# HiveX-Schematic-09.net
KiCad netlist of a schematic drawn in EAGLE
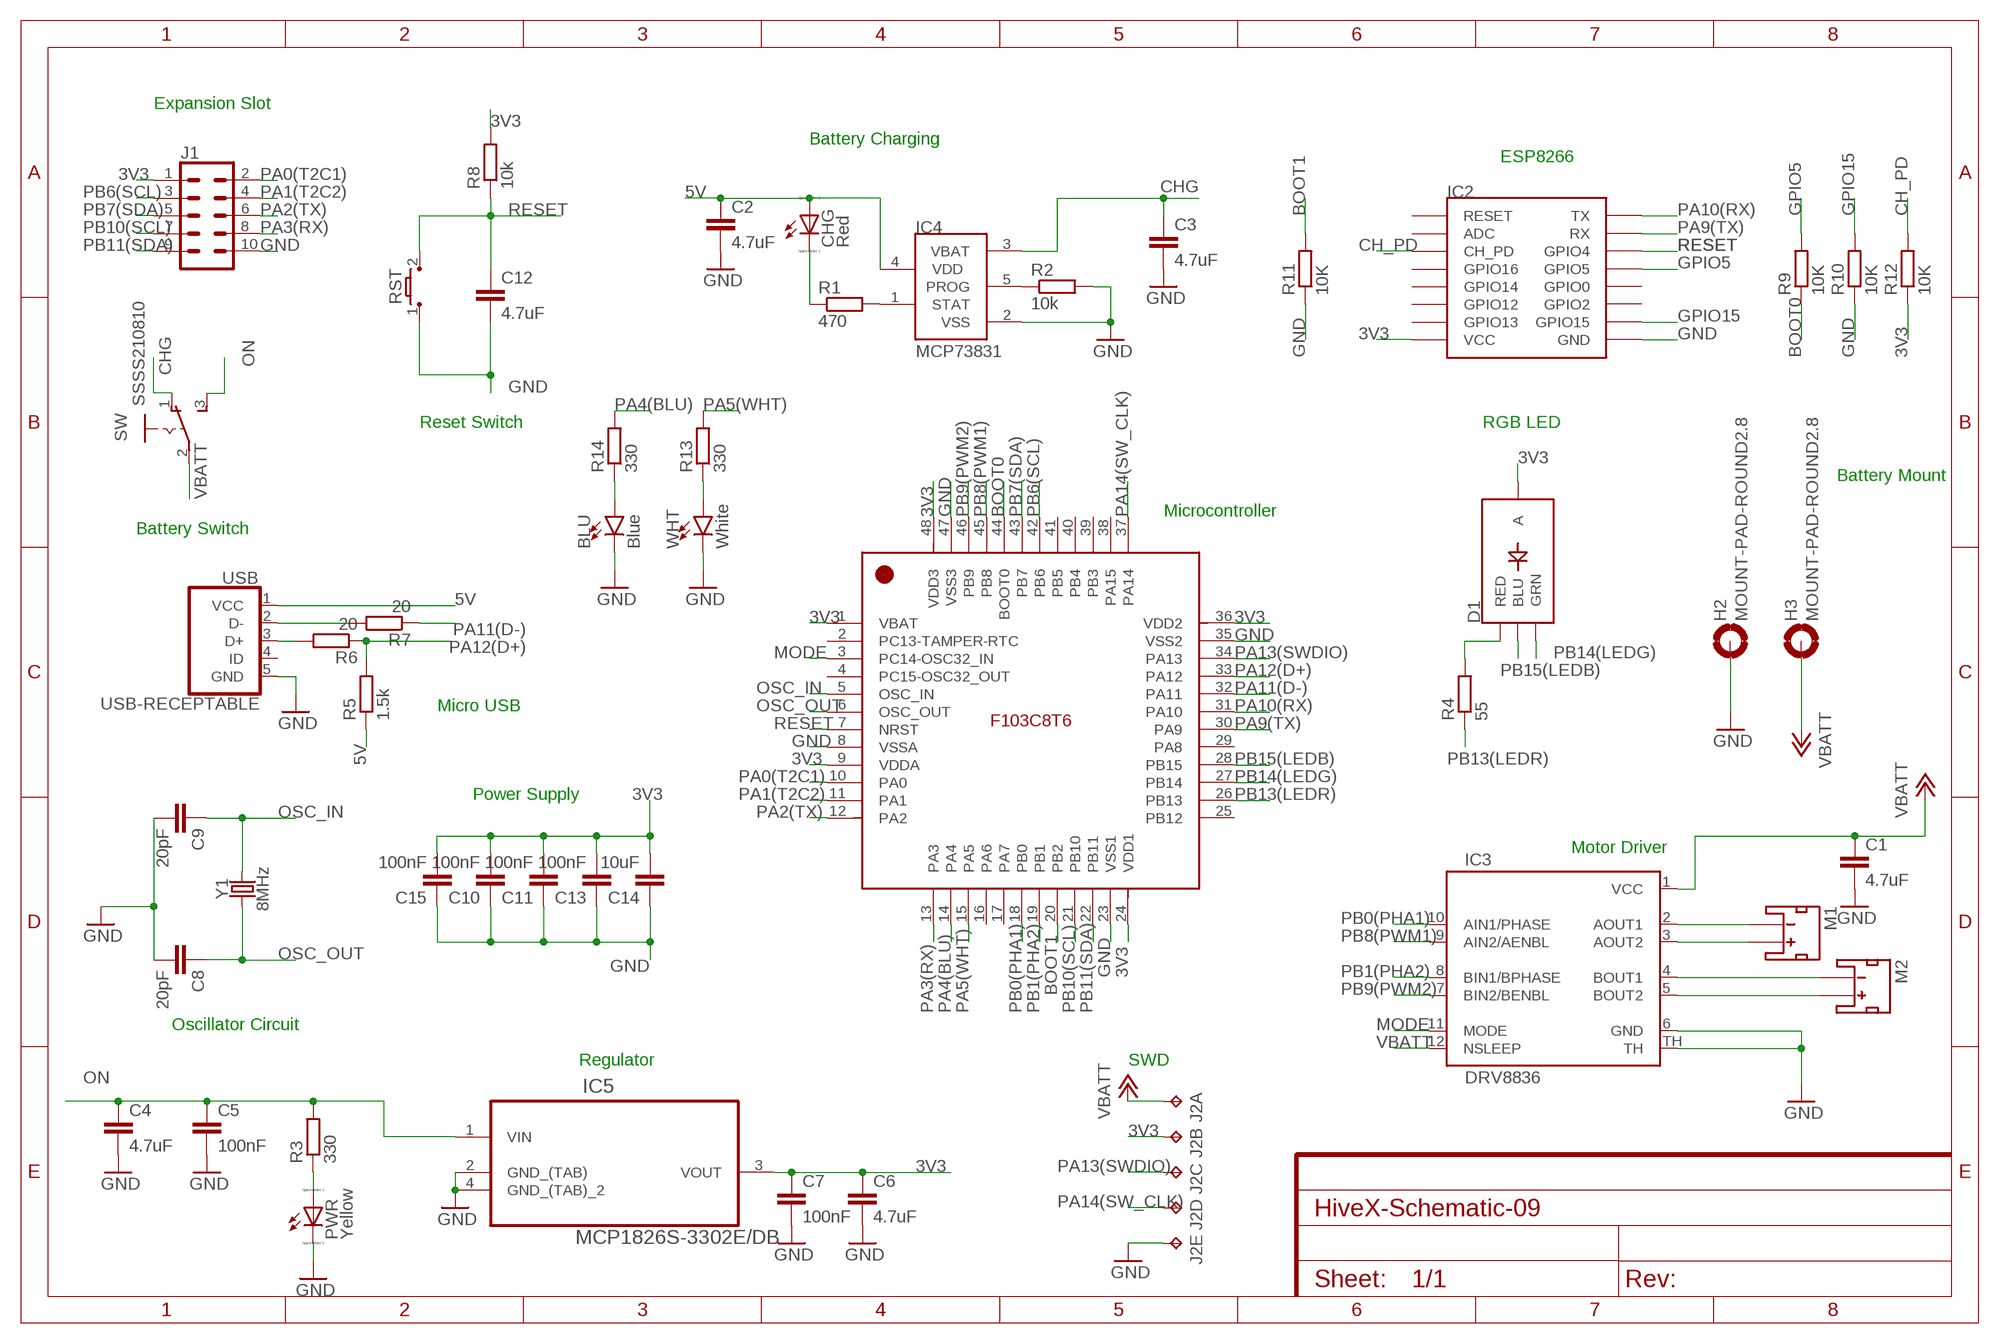
[diagram p0: schematic, sheet 1]

(export (version "E")
  (design (tool "Eeschema 10.0.6"))
  (components
    (comp (ref "BLU")
      (value "Blue")
      (footprint "eagle-import:LED-0603")
      (libsource (lib "eagle-import") (part "LED-BLUE0603"))
    )
    (comp (ref "C1")
      (value "4.7uF")
      (footprint "eagle-import:0603-CAP")
      (libsource (lib "eagle-import") (part "CAP0603-CAP"))
    )
    (comp (ref "C2")
      (value "4.7uF")
      (footprint "eagle-import:0603-CAP")
      (libsource (lib "eagle-import") (part "CAP0603-CAP"))
    )
    (comp (ref "C3")
      (value "4.7uF")
      (footprint "eagle-import:0603-CAP")
      (libsource (lib "eagle-import") (part "CAP0603-CAP"))
    )
    (comp (ref "C4")
      (value "4.7uF")
      (footprint "eagle-import:0603-CAP")
      (libsource (lib "eagle-import") (part "CAP0603-CAP"))
    )
    (comp (ref "C5")
      (value "100nF")
      (footprint "eagle-import:0603-CAP")
      (libsource (lib "eagle-import") (part "CAP0603-CAP"))
    )
    (comp (ref "C6")
      (value "4.7uF")
      (footprint "eagle-import:0603-CAP")
      (libsource (lib "eagle-import") (part "CAP0603-CAP"))
    )
    (comp (ref "C7")
      (value "100nF")
      (footprint "eagle-import:0603-CAP")
      (libsource (lib "eagle-import") (part "CAP0603-CAP"))
    )
    (comp (ref "C8")
      (value "20pF")
      (footprint "eagle-import:0603-CAP")
      (libsource (lib "eagle-import") (part "CAP0603-CAP"))
    )
    (comp (ref "C9")
      (value "20pF")
      (footprint "eagle-import:0603-CAP")
      (libsource (lib "eagle-import") (part "CAP0603-CAP"))
    )
    (comp (ref "C10")
      (value "100nF")
      (footprint "eagle-import:0603-CAP")
      (libsource (lib "eagle-import") (part "CAP0603-CAP"))
    )
    (comp (ref "C11")
      (value "100nF")
      (footprint "eagle-import:0603-CAP")
      (libsource (lib "eagle-import") (part "CAP0603-CAP"))
    )
    (comp (ref "C12")
      (value "4.7uF")
      (footprint "eagle-import:0603-CAP")
      (libsource (lib "eagle-import") (part "CAP0603-CAP"))
    )
    (comp (ref "C13")
      (value "100nF")
      (footprint "eagle-import:0603-CAP")
      (libsource (lib "eagle-import") (part "CAP0603-CAP"))
    )
    (comp (ref "C14")
      (value "10uF")
      (footprint "eagle-import:0603-CAP")
      (libsource (lib "eagle-import") (part "CAP0603-CAP"))
    )
    (comp (ref "C15")
      (value "100nF")
      (footprint "eagle-import:0603-CAP")
      (libsource (lib "eagle-import") (part "CAP0603-CAP"))
    )
    (comp (ref "CHG")
      (value "Red")
      (footprint "eagle-import:LED_SML0603")
      (libsource (lib "eagle-import") (part "LED_ESML0603"))
    )
    (comp (ref "D1")
      (value "LED-RGB-CASMD")
      (footprint "eagle-import:LED-TRICOLOR-SMD")
      (libsource (lib "eagle-import") (part "LED-RGB-CASMD"))
    )
    (comp (ref "H2")
      (value "MOUNT-PAD-ROUND2.8")
      (footprint "eagle-import:2,8-PAD")
      (libsource (lib "eagle-import") (part "MOUNT-PAD-ROUND2.8"))
    )
    (comp (ref "H3")
      (value "MOUNT-PAD-ROUND2.8")
      (footprint "eagle-import:2,8-PAD")
      (libsource (lib "eagle-import") (part "MOUNT-PAD-ROUND2.8"))
    )
    (comp (ref "IC1")
      (value "STM32F103C8T6")
      (footprint "eagle-import:LQFP48_7X7MM_0.5MMPP")
      (fields (field (name "MF") "STMicroelectronics"))
      (libsource (lib "eagle-import") (part "STM32F103C8T6"))
    )
    (comp (ref "IC2")
      (value "ESP12")
      (footprint "eagle-import:ESP12")
      (libsource (lib "eagle-import") (part "ESP12"))
    )
    (comp (ref "IC3")
      (value "DRV8836")
      (footprint "eagle-import:12WSON")
      (libsource (lib "eagle-import") (part "DRV8836"))
    )
    (comp (ref "IC4")
      (value "MCP73831")
      (footprint "eagle-import:SOT23-5L")
      (libsource (lib "eagle-import") (part "MCP73831"))
    )
    (comp (ref "IC5")
      (value "MCP1826S-3302E/DB")
      (footprint "eagle-import:SOT230P700X180-4N")
      (fields (field (name "MF") "Microchip"))
      (libsource (lib "eagle-import") (part "MCP1826S-3302E/DB"))
    )
    (comp (ref "J1")
      (value "CONN_05X2PTH")
      (footprint "eagle-import:2X5")
      (libsource (lib "eagle-import") (part "CONN_05X2PTH"))
    )
    (comp (ref "J2")
      (value "TP5P5-25-13")
      (footprint "eagle-import:P5-25-13")
      (libsource (lib "eagle-import") (part "TP5P5-25-13"))
    )
    (comp (ref "M1")
      (value "JST_2MM_MALE")
      (footprint "eagle-import:JST-2-SMD")
      (libsource (lib "eagle-import") (part "JST_2MM_MALE"))
    )
    (comp (ref "M2")
      (value "JST_2MM_MALE")
      (footprint "eagle-import:JST-2-SMD")
      (libsource (lib "eagle-import") (part "JST_2MM_MALE"))
    )
    (comp (ref "PWR")
      (value "Yellow")
      (footprint "eagle-import:LED_SML0603")
      (libsource (lib "eagle-import") (part "LED_ESML0603"))
    )
    (comp (ref "R1")
      (value "470")
      (footprint "eagle-import:R0603")
      (libsource (lib "eagle-import") (part "resistor_348_R-EU_R0603"))
    )
    (comp (ref "R2")
      (value "10k")
      (footprint "eagle-import:R0603")
      (libsource (lib "eagle-import") (part "resistor_348_R-EU_R0603"))
    )
    (comp (ref "R3")
      (value "330")
      (footprint "eagle-import:R0603")
      (libsource (lib "eagle-import") (part "resistor_348_R-EU_R0603"))
    )
    (comp (ref "R4")
      (value "55")
      (footprint "eagle-import:R0603")
      (libsource (lib "eagle-import") (part "resistor_348_R-EU_R0603"))
    )
    (comp (ref "R5")
      (value "1.5k")
      (footprint "eagle-import:R0603")
      (libsource (lib "eagle-import") (part "resistor_348_R-EU_R0603"))
    )
    (comp (ref "R6")
      (value "20")
      (footprint "eagle-import:R0603")
      (libsource (lib "eagle-import") (part "resistor_348_R-EU_R0603"))
    )
    (comp (ref "R7")
      (value "20")
      (footprint "eagle-import:R0603")
      (libsource (lib "eagle-import") (part "resistor_348_R-EU_R0603"))
    )
    (comp (ref "R8")
      (value "10k")
      (footprint "eagle-import:R0603")
      (libsource (lib "eagle-import") (part "resistor_348_R-EU_R0603"))
    )
    (comp (ref "R9")
      (value "10K")
      (footprint "eagle-import:R0603")
      (libsource (lib "eagle-import") (part "R-EU_R0603"))
    )
    (comp (ref "R10")
      (value "10K")
      (footprint "eagle-import:R0603")
      (libsource (lib "eagle-import") (part "R-EU_R0603"))
    )
    (comp (ref "R11")
      (value "10K")
      (footprint "eagle-import:R0603")
      (libsource (lib "eagle-import") (part "R-EU_R0603"))
    )
    (comp (ref "R12")
      (value "10K")
      (footprint "eagle-import:R0603")
      (libsource (lib "eagle-import") (part "R-EU_R0603"))
    )
    (comp (ref "R13")
      (value "330")
      (footprint "eagle-import:R0603")
      (libsource (lib "eagle-import") (part "resistor_348_R-EU_R0603"))
    )
    (comp (ref "R14")
      (value "330")
      (footprint "eagle-import:R0603")
      (libsource (lib "eagle-import") (part "resistor_348_R-EU_R0603"))
    )
    (comp (ref "RST")
      (value "TL3302-J")
      (footprint "eagle-import:TL3303_J")
      (libsource (lib "eagle-import") (part "TL3302-J"))
    )
    (comp (ref "SW")
      (value "SSSS210810")
      (footprint "eagle-import:SSSS210810")
      (libsource (lib "eagle-import") (part "SSSS210810"))
    )
    (comp (ref "USB")
      (value "USB-RECEPTABLE")
      (footprint "eagle-import:FCI-10103594-0001LF")
      (libsource (lib "eagle-import") (part "USB-RECEPTABLE"))
    )
    (comp (ref "WHT")
      (value "White")
      (footprint "eagle-import:LED-0603")
      (libsource (lib "eagle-import") (part "LED-WHITE0603"))
    )
    (comp (ref "Y1")
      (value "8MHz")
      (footprint "eagle-import:CRYSTAL-SMD-5X3.2-4PAD")
      (libsource (lib "eagle-import") (part "CRYSTAL-8MHZSMD-5X3.2"))
    )
  )
  (nets
    (net (code "1") (name "/3V3") (class "Default")
      (node (ref "C10") (pin "2") (pinfunction "2_2") (pintype "passive"))
      (node (ref "C11") (pin "2") (pinfunction "2_2") (pintype "passive"))
      (node (ref "C13") (pin "2") (pinfunction "2_2") (pintype "passive"))
      (node (ref "C14") (pin "2") (pinfunction "2_2") (pintype "passive"))
      (node (ref "C15") (pin "2") (pinfunction "2_2") (pintype "passive"))
      (node (ref "C6") (pin "1") (pinfunction "1_1") (pintype "passive"))
      (node (ref "C7") (pin "1") (pinfunction "1_1") (pintype "passive"))
      (node (ref "D1") (pin "A") (pinfunction "A_A") (pintype "bidirectional"))
      (node (ref "IC1") (pin "1") (pinfunction "VBAT_1") (pintype "bidirectional"))
      (node (ref "IC1") (pin "24") (pinfunction "VDD1_24") (pintype "bidirectional"))
      (node (ref "IC1") (pin "36") (pinfunction "VDD2_36") (pintype "bidirectional"))
      (node (ref "IC1") (pin "48") (pinfunction "VDD3_48") (pintype "bidirectional"))
      (node (ref "IC1") (pin "9") (pinfunction "VDDA_9") (pintype "bidirectional"))
      (node (ref "IC2") (pin "VCC") (pinfunction "VCC_VCC") (pintype "bidirectional"))
      (node (ref "IC5") (pin "3") (pinfunction "VOUT_3") (pintype "output"))
      (node (ref "J1") (pin "1") (pinfunction "1_1") (pintype "passive"))
      (node (ref "J2") (pin "TP-2") (pinfunction "TP_TP-2") (pintype "input"))
      (node (ref "R12") (pin "1") (pinfunction "1_1") (pintype "passive"))
      (node (ref "R8") (pin "2") (pinfunction "2_2") (pintype "passive"))
    )
    (net (code "2") (name "/5V") (class "Default")
      (node (ref "C2") (pin "1") (pinfunction "1_1") (pintype "passive"))
      (node (ref "CHG") (pin "A") (pinfunction "A_A") (pintype "passive"))
      (node (ref "IC4") (pin "4") (pinfunction "VDD_4") (pintype "bidirectional"))
      (node (ref "R5") (pin "1") (pinfunction "1_1") (pintype "passive"))
      (node (ref "USB") (pin "1") (pinfunction "VCC_1") (pintype "bidirectional"))
    )
    (net (code "3") (name "/BOOT0") (class "Default")
      (node (ref "IC1") (pin "44") (pinfunction "BOOT0_44") (pintype "bidirectional"))
      (node (ref "R9") (pin "1") (pinfunction "1_1") (pintype "passive"))
    )
    (net (code "4") (name "/BOOT1") (class "Default")
      (node (ref "IC1") (pin "20") (pinfunction "PB2_20") (pintype "bidirectional"))
      (node (ref "R11") (pin "2") (pinfunction "2_2") (pintype "passive"))
    )
    (net (code "5") (name "/CHG") (class "Default")
      (node (ref "C3") (pin "1") (pinfunction "1_1") (pintype "passive"))
      (node (ref "IC4") (pin "3") (pinfunction "VBAT_3") (pintype "bidirectional"))
      (node (ref "SW") (pin "1") (pinfunction "NC_1") (pintype "passive"))
    )
    (net (code "6") (name "/CH_PD") (class "Default")
      (node (ref "IC2") (pin "CH_PD") (pinfunction "CH_PD_CH_PD") (pintype "bidirectional"))
      (node (ref "R12") (pin "2") (pinfunction "2_2") (pintype "passive"))
    )
    (net (code "7") (name "/GPIO5") (class "Default")
      (node (ref "IC2") (pin "GPIO5") (pinfunction "GPIO5_GPIO5") (pintype "bidirectional"))
      (node (ref "R9") (pin "2") (pinfunction "2_2") (pintype "passive"))
    )
    (net (code "8") (name "/GPIO15") (class "Default")
      (node (ref "IC2") (pin "GPIO15") (pinfunction "GPIO15_GPIO15") (pintype "bidirectional"))
      (node (ref "R10") (pin "2") (pinfunction "2_2") (pintype "passive"))
    )
    (net (code "9") (name "/MODE") (class "Default")
      (node (ref "IC1") (pin "3") (pinfunction "PC14-OSC32_IN_3") (pintype "bidirectional"))
      (node (ref "IC3") (pin "11") (pinfunction "MODE_11") (pintype "bidirectional"))
    )
    (net (code "10") (name "/ON") (class "Default")
      (node (ref "C4") (pin "1") (pinfunction "1_1") (pintype "passive"))
      (node (ref "C5") (pin "1") (pinfunction "1_1") (pintype "passive"))
      (node (ref "IC5") (pin "1") (pinfunction "VIN_1") (pintype "input"))
      (node (ref "R3") (pin "2") (pinfunction "2_2") (pintype "passive"))
      (node (ref "SW") (pin "3") (pinfunction "NO_3") (pintype "passive"))
    )
    (net (code "11") (name "/OSC_IN") (class "Default")
      (node (ref "C9") (pin "1") (pinfunction "1_1") (pintype "passive"))
      (node (ref "IC1") (pin "5") (pinfunction "OSC_IN_5") (pintype "bidirectional"))
      (node (ref "Y1") (pin "3") (pinfunction "2_3") (pintype "passive"))
    )
    (net (code "12") (name "/OSC_OUT") (class "Default")
      (node (ref "C8") (pin "1") (pinfunction "1_1") (pintype "passive"))
      (node (ref "IC1") (pin "6") (pinfunction "OSC_OUT_6") (pintype "bidirectional"))
      (node (ref "Y1") (pin "1") (pinfunction "1_1") (pintype "passive"))
    )
    (net (code "13") (name "/PA0(T2C1)") (class "Default")
      (node (ref "IC1") (pin "10") (pinfunction "PA0_10") (pintype "bidirectional"))
      (node (ref "J1") (pin "2") (pinfunction "2_2") (pintype "passive"))
    )
    (net (code "14") (name "/PA1(T2C2)") (class "Default")
      (node (ref "IC1") (pin "11") (pinfunction "PA1_11") (pintype "bidirectional"))
      (node (ref "J1") (pin "4") (pinfunction "4_4") (pintype "passive"))
    )
    (net (code "15") (name "/PA2(TX)") (class "Default")
      (node (ref "IC1") (pin "12") (pinfunction "PA2_12") (pintype "bidirectional"))
      (node (ref "J1") (pin "6") (pinfunction "6_6") (pintype "passive"))
    )
    (net (code "16") (name "/PA3(RX)") (class "Default")
      (node (ref "IC1") (pin "13") (pinfunction "PA3_13") (pintype "bidirectional"))
      (node (ref "J1") (pin "8") (pinfunction "8_8") (pintype "passive"))
    )
    (net (code "17") (name "/PA4(BLU)") (class "Default")
      (node (ref "IC1") (pin "14") (pinfunction "PA4_14") (pintype "bidirectional"))
      (node (ref "R14") (pin "2") (pinfunction "2_2") (pintype "passive"))
    )
    (net (code "18") (name "/PA5(WHT)") (class "Default")
      (node (ref "IC1") (pin "15") (pinfunction "PA5_15") (pintype "bidirectional"))
      (node (ref "R13") (pin "2") (pinfunction "2_2") (pintype "passive"))
    )
    (net (code "19") (name "/PA9(TX)") (class "Default")
      (node (ref "IC1") (pin "30") (pinfunction "PA9_30") (pintype "bidirectional"))
      (node (ref "IC2") (pin "RX") (pinfunction "RX_RX") (pintype "bidirectional"))
    )
    (net (code "20") (name "/PA10(RX)") (class "Default")
      (node (ref "IC1") (pin "31") (pinfunction "PA10_31") (pintype "bidirectional"))
      (node (ref "IC2") (pin "TX") (pinfunction "TX_TX") (pintype "bidirectional"))
    )
    (net (code "21") (name "/PA11(D-)") (class "Default")
      (node (ref "IC1") (pin "32") (pinfunction "PA11_32") (pintype "bidirectional"))
      (node (ref "R7") (pin "1") (pinfunction "1_1") (pintype "passive"))
    )
    (net (code "22") (name "/PA12(D+)") (class "Default")
      (node (ref "IC1") (pin "33") (pinfunction "PA12_33") (pintype "bidirectional"))
      (node (ref "R5") (pin "2") (pinfunction "2_2") (pintype "passive"))
      (node (ref "R6") (pin "1") (pinfunction "1_1") (pintype "passive"))
    )
    (net (code "23") (name "/PA13(SWDIO)") (class "Default")
      (node (ref "IC1") (pin "34") (pinfunction "PA13_34") (pintype "bidirectional"))
      (node (ref "J2") (pin "TP-3") (pinfunction "TP_TP-3") (pintype "input"))
    )
    (net (code "24") (name "/PA14(SW_CLK)") (class "Default")
      (node (ref "IC1") (pin "37") (pinfunction "PA14_37") (pintype "bidirectional"))
      (node (ref "J2") (pin "TP-4") (pinfunction "TP_TP-4") (pintype "input"))
    )
    (net (code "25") (name "/PB0(PHA1)") (class "Default")
      (node (ref "IC1") (pin "18") (pinfunction "PB0_18") (pintype "bidirectional"))
      (node (ref "IC3") (pin "10") (pinfunction "AIN1/PHASE_10") (pintype "bidirectional"))
    )
    (net (code "26") (name "/PB1(PHA2)") (class "Default")
      (node (ref "IC1") (pin "19") (pinfunction "PB1_19") (pintype "bidirectional"))
      (node (ref "IC3") (pin "8") (pinfunction "BIN1/BPHASE_8") (pintype "bidirectional"))
    )
    (net (code "27") (name "/PB6(SCL)") (class "Default")
      (node (ref "IC1") (pin "42") (pinfunction "PB6_42") (pintype "bidirectional"))
      (node (ref "J1") (pin "3") (pinfunction "3_3") (pintype "passive"))
    )
    (net (code "28") (name "/PB7(SDA)") (class "Default")
      (node (ref "IC1") (pin "43") (pinfunction "PB7_43") (pintype "bidirectional"))
      (node (ref "J1") (pin "5") (pinfunction "5_5") (pintype "passive"))
    )
    (net (code "29") (name "/PB8(PWM1)") (class "Default")
      (node (ref "IC1") (pin "45") (pinfunction "PB8_45") (pintype "bidirectional"))
      (node (ref "IC3") (pin "9") (pinfunction "AIN2/AENBL_9") (pintype "bidirectional"))
    )
    (net (code "30") (name "/PB9(PWM2)") (class "Default")
      (node (ref "IC1") (pin "46") (pinfunction "PB9_46") (pintype "bidirectional"))
      (node (ref "IC3") (pin "7") (pinfunction "BIN2/BENBL_7") (pintype "bidirectional"))
    )
    (net (code "31") (name "/PB10(SCL)") (class "Default")
      (node (ref "IC1") (pin "21") (pinfunction "PB10_21") (pintype "bidirectional"))
      (node (ref "J1") (pin "7") (pinfunction "7_7") (pintype "passive"))
    )
    (net (code "32") (name "/PB11(SDA)") (class "Default")
      (node (ref "IC1") (pin "22") (pinfunction "PB11_22") (pintype "bidirectional"))
      (node (ref "J1") (pin "9") (pinfunction "9_9") (pintype "passive"))
    )
    (net (code "33") (name "/PB13(LEDR)") (class "Default")
      (node (ref "IC1") (pin "26") (pinfunction "PB13_26") (pintype "bidirectional"))
      (node (ref "R4") (pin "1") (pinfunction "1_1") (pintype "passive"))
    )
    (net (code "34") (name "/PB14(LEDG)") (class "Default")
      (node (ref "D1") (pin "G") (pinfunction "GRN_G") (pintype "bidirectional"))
      (node (ref "IC1") (pin "27") (pinfunction "PB14_27") (pintype "bidirectional"))
    )
    (net (code "35") (name "/PB15(LEDB)") (class "Default")
      (node (ref "D1") (pin "B") (pinfunction "BLU_B") (pintype "bidirectional"))
      (node (ref "IC1") (pin "28") (pinfunction "PB15_28") (pintype "bidirectional"))
    )
    (net (code "36") (name "/RESET") (class "Default")
      (node (ref "C12") (pin "1") (pinfunction "1_1") (pintype "passive"))
      (node (ref "IC1") (pin "7") (pinfunction "NRST_7") (pintype "bidirectional"))
      (node (ref "IC2") (pin "GPIO4") (pinfunction "GPIO4_GPIO4") (pintype "bidirectional"))
      (node (ref "R8") (pin "1") (pinfunction "1_1") (pintype "passive"))
      (node (ref "RST") (pin "2") (pinfunction "2_2") (pintype "passive"))
    )
    (net (code "37") (name "GND") (class "Default")
      (node (ref "BLU") (pin "C") (pinfunction "C_C") (pintype "passive"))
      (node (ref "C1") (pin "2") (pinfunction "2_2") (pintype "passive"))
      (node (ref "C10") (pin "1") (pinfunction "1_1") (pintype "passive"))
      (node (ref "C11") (pin "1") (pinfunction "1_1") (pintype "passive"))
      (node (ref "C12") (pin "2") (pinfunction "2_2") (pintype "passive"))
      (node (ref "C13") (pin "1") (pinfunction "1_1") (pintype "passive"))
      (node (ref "C14") (pin "1") (pinfunction "1_1") (pintype "passive"))
      (node (ref "C15") (pin "1") (pinfunction "1_1") (pintype "passive"))
      (node (ref "C2") (pin "2") (pinfunction "2_2") (pintype "passive"))
      (node (ref "C3") (pin "2") (pinfunction "2_2") (pintype "passive"))
      (node (ref "C4") (pin "2") (pinfunction "2_2") (pintype "passive"))
      (node (ref "C5") (pin "2") (pinfunction "2_2") (pintype "passive"))
      (node (ref "C6") (pin "2") (pinfunction "2_2") (pintype "passive"))
      (node (ref "C7") (pin "2") (pinfunction "2_2") (pintype "passive"))
      (node (ref "C8") (pin "2") (pinfunction "2_2") (pintype "passive"))
      (node (ref "C9") (pin "2") (pinfunction "2_2") (pintype "passive"))
      (node (ref "H2") (pin "B2,8") (pinfunction "MOUNT_B2,8") (pintype "passive"))
      (node (ref "IC1") (pin "23") (pinfunction "VSS1_23") (pintype "bidirectional"))
      (node (ref "IC1") (pin "35") (pinfunction "VSS2_35") (pintype "bidirectional"))
      (node (ref "IC1") (pin "47") (pinfunction "VSS3_47") (pintype "bidirectional"))
      (node (ref "IC1") (pin "8") (pinfunction "VSSA_8") (pintype "bidirectional"))
      (node (ref "IC2") (pin "GND") (pinfunction "GND_GND") (pintype "bidirectional"))
      (node (ref "IC3") (pin "6") (pinfunction "GND_6") (pintype "bidirectional"))
      (node (ref "IC3") (pin "TH") (pinfunction "TH_TH") (pintype "bidirectional"))
      (node (ref "IC4") (pin "2") (pinfunction "VSS_2") (pintype "bidirectional"))
      (node (ref "IC5") (pin "2") (pinfunction "GND_(TAB)_2") (pintype "passive"))
      (node (ref "IC5") (pin "4") (pinfunction "GND_(TAB)_2_4") (pintype "passive"))
      (node (ref "J1") (pin "10") (pinfunction "10_10") (pintype "passive"))
      (node (ref "J2") (pin "TP-5") (pinfunction "TP_TP-5") (pintype "input"))
      (node (ref "PWR") (pin "C") (pinfunction "C_C") (pintype "passive"))
      (node (ref "R10") (pin "1") (pinfunction "1_1") (pintype "passive"))
      (node (ref "R11") (pin "1") (pinfunction "1_1") (pintype "passive"))
      (node (ref "R2") (pin "2") (pinfunction "2_2") (pintype "passive"))
      (node (ref "RST") (pin "1") (pinfunction "1_1") (pintype "passive"))
      (node (ref "USB") (pin "5") (pinfunction "GND_5") (pintype "bidirectional"))
      (node (ref "WHT") (pin "C") (pinfunction "C_C") (pintype "passive"))
    )
    (net (code "38") (name "Net-(BLU-PadA)") (class "Default")
      (node (ref "BLU") (pin "A") (pinfunction "A_A") (pintype "passive"))
      (node (ref "R14") (pin "1") (pinfunction "1_1") (pintype "passive"))
    )
    (net (code "39") (name "Net-(CHG-PadC)") (class "Default")
      (node (ref "CHG") (pin "C") (pinfunction "C_C") (pintype "passive"))
      (node (ref "R1") (pin "1") (pinfunction "1_1") (pintype "passive"))
    )
    (net (code "40") (name "Net-(D1-RED)") (class "Default")
      (node (ref "D1") (pin "R") (pinfunction "RED_R") (pintype "bidirectional"))
      (node (ref "R4") (pin "2") (pinfunction "2_2") (pintype "passive"))
    )
    (net (code "41") (name "Net-(IC3-AOUT1)") (class "Default")
      (node (ref "IC3") (pin "2") (pinfunction "AOUT1_2") (pintype "bidirectional"))
      (node (ref "M1") (pin "1") (pinfunction "-_1") (pintype "bidirectional"))
    )
    (net (code "42") (name "Net-(IC3-AOUT2)") (class "Default")
      (node (ref "IC3") (pin "3") (pinfunction "AOUT2_3") (pintype "bidirectional"))
      (node (ref "M1") (pin "2") (pinfunction "+_2") (pintype "bidirectional"))
    )
    (net (code "43") (name "Net-(IC3-BOUT1)") (class "Default")
      (node (ref "IC3") (pin "4") (pinfunction "BOUT1_4") (pintype "bidirectional"))
      (node (ref "M2") (pin "1") (pinfunction "-_1") (pintype "bidirectional"))
    )
    (net (code "44") (name "Net-(IC3-BOUT2)") (class "Default")
      (node (ref "IC3") (pin "5") (pinfunction "BOUT2_5") (pintype "bidirectional"))
      (node (ref "M2") (pin "2") (pinfunction "+_2") (pintype "bidirectional"))
    )
    (net (code "45") (name "Net-(IC4-PROG)") (class "Default")
      (node (ref "IC4") (pin "5") (pinfunction "PROG_5") (pintype "bidirectional"))
      (node (ref "R2") (pin "1") (pinfunction "1_1") (pintype "passive"))
    )
    (net (code "46") (name "Net-(IC4-STAT)") (class "Default")
      (node (ref "IC4") (pin "1") (pinfunction "STAT_1") (pintype "bidirectional"))
      (node (ref "R1") (pin "2") (pinfunction "2_2") (pintype "passive"))
    )
    (net (code "47") (name "Net-(PWR-PadA)") (class "Default")
      (node (ref "PWR") (pin "A") (pinfunction "A_A") (pintype "passive"))
      (node (ref "R3") (pin "1") (pinfunction "1_1") (pintype "passive"))
    )
    (net (code "48") (name "Net-(R13-Pad1)") (class "Default")
      (node (ref "R13") (pin "1") (pinfunction "1_1") (pintype "passive"))
      (node (ref "WHT") (pin "A") (pinfunction "A_A") (pintype "passive"))
    )
    (net (code "49") (name "Net-(USB-D+)") (class "Default")
      (node (ref "R6") (pin "2") (pinfunction "2_2") (pintype "passive"))
      (node (ref "USB") (pin "3") (pinfunction "D+_3") (pintype "bidirectional"))
    )
    (net (code "50") (name "Net-(USB-D-)") (class "Default")
      (node (ref "R7") (pin "2") (pinfunction "2_2") (pintype "passive"))
      (node (ref "USB") (pin "2") (pinfunction "D-_2") (pintype "bidirectional"))
    )
    (net (code "51") (name "VBATT") (class "Default")
      (node (ref "C1") (pin "1") (pinfunction "1_1") (pintype "passive"))
      (node (ref "H3") (pin "B2,8") (pinfunction "MOUNT_B2,8") (pintype "passive"))
      (node (ref "IC3") (pin "1") (pinfunction "VCC_1") (pintype "bidirectional"))
      (node (ref "IC3") (pin "12") (pinfunction "NSLEEP_12") (pintype "bidirectional"))
      (node (ref "J2") (pin "TP-1") (pinfunction "TP_TP-1") (pintype "input"))
      (node (ref "SW") (pin "2") (pinfunction "COM_2") (pintype "passive"))
    )
    (net (code "52") (name "unconnected-(IC1-PA6-Pad16)") (class "Default")
      (node (ref "IC1") (pin "16") (pinfunction "PA6_16") (pintype "bidirectional"))
    )
    (net (code "53") (name "unconnected-(IC1-PA7-Pad17)") (class "Default")
      (node (ref "IC1") (pin "17") (pinfunction "PA7_17") (pintype "bidirectional"))
    )
    (net (code "54") (name "unconnected-(IC1-PA8-Pad29)") (class "Default")
      (node (ref "IC1") (pin "29") (pinfunction "PA8_29") (pintype "bidirectional"))
    )
    (net (code "55") (name "unconnected-(IC1-PA15-Pad38)") (class "Default")
      (node (ref "IC1") (pin "38") (pinfunction "PA15_38") (pintype "bidirectional"))
    )
    (net (code "56") (name "unconnected-(IC1-PB3-Pad39)") (class "Default")
      (node (ref "IC1") (pin "39") (pinfunction "PB3_39") (pintype "bidirectional"))
    )
    (net (code "57") (name "unconnected-(IC1-PB4-Pad40)") (class "Default")
      (node (ref "IC1") (pin "40") (pinfunction "PB4_40") (pintype "bidirectional"))
    )
    (net (code "58") (name "unconnected-(IC1-PB5-Pad41)") (class "Default")
      (node (ref "IC1") (pin "41") (pinfunction "PB5_41") (pintype "bidirectional"))
    )
    (net (code "59") (name "unconnected-(IC1-PB12-Pad25)") (class "Default")
      (node (ref "IC1") (pin "25") (pinfunction "PB12_25") (pintype "bidirectional"))
    )
    (net (code "60") (name "unconnected-(IC1-PC13-TAMPER-RTC-Pad2)") (class "Default")
      (node (ref "IC1") (pin "2") (pinfunction "PC13-TAMPER-RTC_2") (pintype "bidirectional"))
    )
    (net (code "61") (name "unconnected-(IC1-PC15-OSC32_OUT-Pad4)") (class "Default")
      (node (ref "IC1") (pin "4") (pinfunction "PC15-OSC32_OUT_4") (pintype "bidirectional"))
    )
    (net (code "62") (name "unconnected-(IC2-PadADC)") (class "Default")
      (node (ref "IC2") (pin "ADC") (pinfunction "ADC_ADC") (pintype "bidirectional"))
    )
    (net (code "63") (name "unconnected-(IC2-PadGPIO0)") (class "Default")
      (node (ref "IC2") (pin "GPIO0") (pinfunction "GPIO0_GPIO0") (pintype "bidirectional"))
    )
    (net (code "64") (name "unconnected-(IC2-PadGPIO2)") (class "Default")
      (node (ref "IC2") (pin "GPIO2") (pinfunction "GPIO2_GPIO2") (pintype "bidirectional"))
    )
    (net (code "65") (name "unconnected-(IC2-PadGPIO12)") (class "Default")
      (node (ref "IC2") (pin "GPIO12") (pinfunction "GPIO12_GPIO12") (pintype "bidirectional"))
    )
    (net (code "66") (name "unconnected-(IC2-PadGPIO13)") (class "Default")
      (node (ref "IC2") (pin "GPIO13") (pinfunction "GPIO13_GPIO13") (pintype "bidirectional"))
    )
    (net (code "67") (name "unconnected-(IC2-PadGPIO14)") (class "Default")
      (node (ref "IC2") (pin "GPIO14") (pinfunction "GPIO14_GPIO14") (pintype "bidirectional"))
    )
    (net (code "68") (name "unconnected-(IC2-PadGPIO16)") (class "Default")
      (node (ref "IC2") (pin "GPIO16") (pinfunction "GPIO16_GPIO16") (pintype "bidirectional"))
    )
    (net (code "69") (name "unconnected-(IC2-PadRESET)") (class "Default")
      (node (ref "IC2") (pin "RESET") (pinfunction "RESET_RESET") (pintype "bidirectional"))
    )
    (net (code "70") (name "unconnected-(M1-PAD1-PadNC1)") (class "Default")
      (node (ref "M1") (pin "NC1") (pinfunction "PAD1_NC1") (pintype "bidirectional"))
    )
    (net (code "71") (name "unconnected-(M1-PAD2-PadNC2)") (class "Default")
      (node (ref "M1") (pin "NC2") (pinfunction "PAD2_NC2") (pintype "bidirectional"))
    )
    (net (code "72") (name "unconnected-(M2-PAD1-PadNC1)") (class "Default")
      (node (ref "M2") (pin "NC1") (pinfunction "PAD1_NC1") (pintype "bidirectional"))
    )
    (net (code "73") (name "unconnected-(M2-PAD2-PadNC2)") (class "Default")
      (node (ref "M2") (pin "NC2") (pinfunction "PAD2_NC2") (pintype "bidirectional"))
    )
    (net (code "74") (name "unconnected-(USB-ID-Pad4)") (class "Default")
      (node (ref "USB") (pin "4") (pinfunction "ID_4") (pintype "bidirectional"))
    )
  )
)
